# 2-psg-plain2.net
KiCad netlist of a schematic drawn in EAGLE
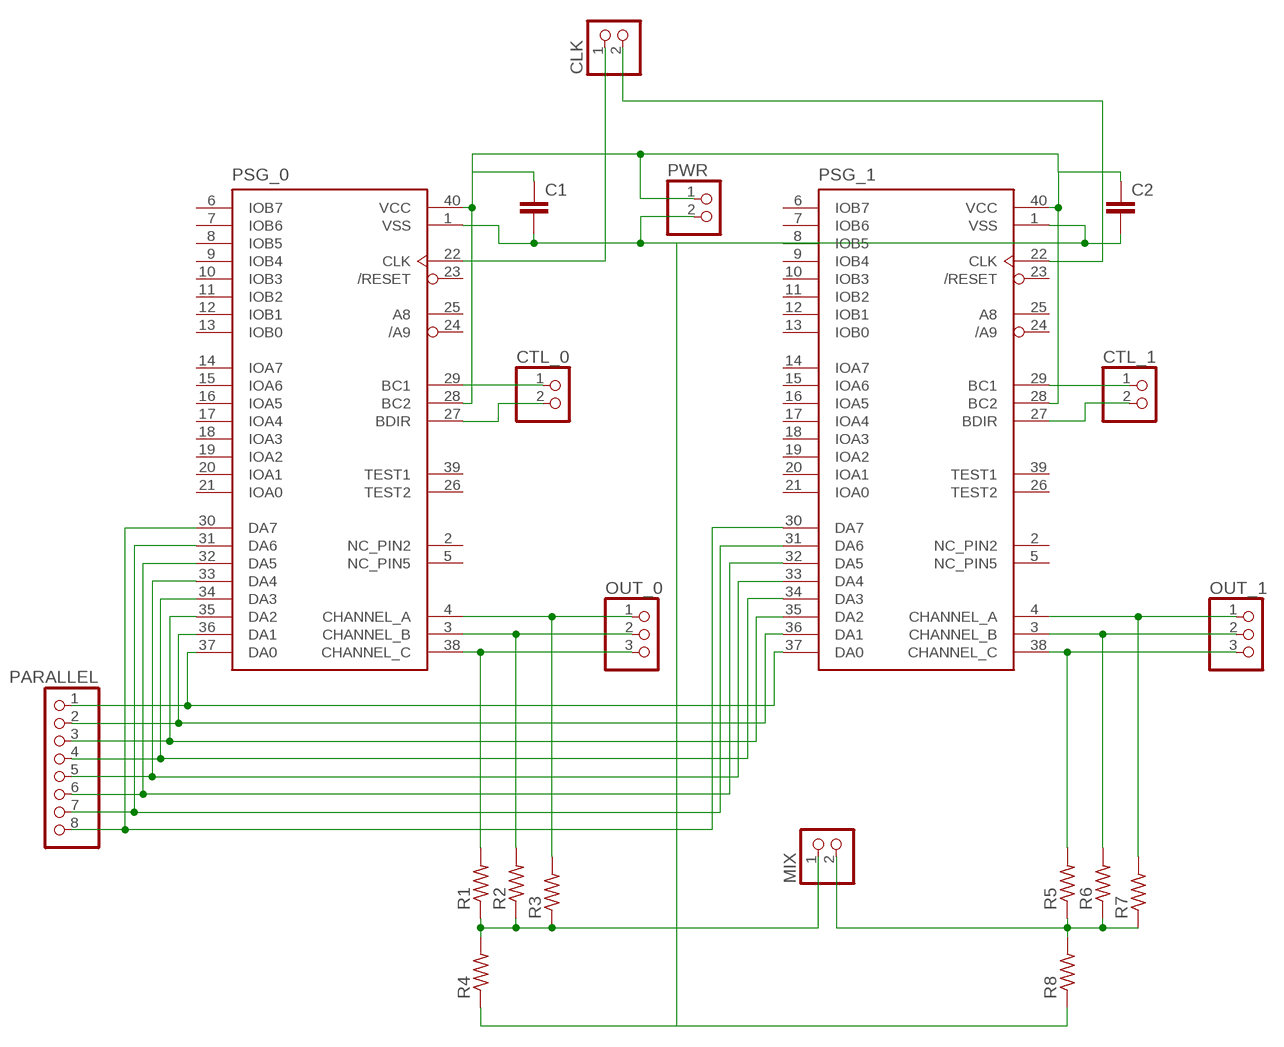
[diagram p0: schematic, sheet 1]

(export (version "E")
  (design (tool "Eeschema 10.0.6"))
  (components
    (comp (ref "C1")
      (value "050X030_0251")
      (footprint "eagle-import:050X030_025")
      (libsource (lib "eagle-import") (part "050X030_0251"))
    )
    (comp (ref "C2")
      (value "050X030_0251")
      (footprint "eagle-import:050X030_025")
      (libsource (lib "eagle-import") (part "050X030_0251"))
    )
    (comp (ref "CLK")
      (value "PINHD-1X2")
      (footprint "eagle-import:1X02")
      (libsource (lib "eagle-import") (part "PINHD-1X2"))
    )
    (comp (ref "CTL_0")
      (value "PINHD-1X2")
      (footprint "eagle-import:1X02")
      (libsource (lib "eagle-import") (part "PINHD-1X2"))
    )
    (comp (ref "CTL_1")
      (value "PINHD-1X2")
      (footprint "eagle-import:1X02")
      (libsource (lib "eagle-import") (part "PINHD-1X2"))
    )
    (comp (ref "MIX")
      (value "PINHD-1X2")
      (footprint "eagle-import:1X02")
      (libsource (lib "eagle-import") (part "PINHD-1X2"))
    )
    (comp (ref "OUT_0")
      (value "PINHD-1X3")
      (footprint "eagle-import:1X03")
      (libsource (lib "eagle-import") (part "PINHD-1X3"))
    )
    (comp (ref "OUT_1")
      (value "PINHD-1X3")
      (footprint "eagle-import:1X03")
      (libsource (lib "eagle-import") (part "PINHD-1X3"))
    )
    (comp (ref "PARALLEL")
      (value "PINHD-1X8")
      (footprint "eagle-import:1X08")
      (libsource (lib "eagle-import") (part "PINHD-1X8"))
    )
    (comp (ref "PSG_0")
      (value "AY-3-8910")
      (footprint "eagle-import:DIL40")
      (libsource (lib "eagle-import") (part "AY-3-8910"))
    )
    (comp (ref "PSG_1")
      (value "AY-3-8910")
      (footprint "eagle-import:DIL40")
      (libsource (lib "eagle-import") (part "AY-3-8910"))
    )
    (comp (ref "PWR")
      (value "PINHD-1X2")
      (footprint "eagle-import:1X02")
      (libsource (lib "eagle-import") (part "PINHD-1X2"))
    )
    (comp (ref "R1")
      (value "6MM.3")
      (footprint "eagle-import:R0207_3")
      (libsource (lib "eagle-import") (part "6MM.3"))
    )
    (comp (ref "R2")
      (value "6MM.3")
      (footprint "eagle-import:R0207_3")
      (libsource (lib "eagle-import") (part "6MM.3"))
    )
    (comp (ref "R3")
      (value "6MM.3")
      (footprint "eagle-import:R0207_3")
      (libsource (lib "eagle-import") (part "6MM.3"))
    )
    (comp (ref "R4")
      (value "6MM.3")
      (footprint "eagle-import:R0207_3")
      (libsource (lib "eagle-import") (part "6MM.3"))
    )
    (comp (ref "R5")
      (value "6MM.3")
      (footprint "eagle-import:R0207_3")
      (libsource (lib "eagle-import") (part "6MM.3"))
    )
    (comp (ref "R6")
      (value "6MM.3")
      (footprint "eagle-import:R0207_3")
      (libsource (lib "eagle-import") (part "6MM.3"))
    )
    (comp (ref "R7")
      (value "6MM.3")
      (footprint "eagle-import:R0207_3")
      (libsource (lib "eagle-import") (part "6MM.3"))
    )
    (comp (ref "R8")
      (value "6MM.3")
      (footprint "eagle-import:R0207_3")
      (libsource (lib "eagle-import") (part "6MM.3"))
    )
  )
  (nets
    (net (code "1") (name "Net-(MIX-Pad1)") (class "Default")
      (node (ref "MIX") (pin "1") (pinfunction "1_1") (pintype "passive"))
      (node (ref "R1") (pin "1") (pinfunction "1_1") (pintype "passive"))
      (node (ref "R2") (pin "1") (pinfunction "1_1") (pintype "passive"))
      (node (ref "R3") (pin "1") (pinfunction "1_1") (pintype "passive"))
      (node (ref "R4") (pin "2") (pinfunction "2_2") (pintype "passive"))
    )
    (net (code "2") (name "Net-(MIX-Pad2)") (class "Default")
      (node (ref "MIX") (pin "2") (pinfunction "2_2") (pintype "passive"))
      (node (ref "R5") (pin "1") (pinfunction "1_1") (pintype "passive"))
      (node (ref "R6") (pin "1") (pinfunction "1_1") (pintype "passive"))
      (node (ref "R7") (pin "1") (pinfunction "1_1") (pintype "passive"))
      (node (ref "R8") (pin "2") (pinfunction "2_2") (pintype "passive"))
    )
    (net (code "3") (name "Net-(PSG_0-BC1)") (class "Default")
      (node (ref "CTL_0") (pin "1") (pinfunction "1_1") (pintype "passive"))
      (node (ref "PSG_0") (pin "29") (pinfunction "BC1_29") (pintype "input"))
    )
    (net (code "4") (name "Net-(PSG_0-BC2)") (class "Default")
      (node (ref "C1") (pin "1") (pinfunction "1_1") (pintype "passive"))
      (node (ref "C2") (pin "1") (pinfunction "1_1") (pintype "passive"))
      (node (ref "PSG_0") (pin "28") (pinfunction "BC2_28") (pintype "input"))
      (node (ref "PSG_0") (pin "40") (pinfunction "VCC_40") (pintype "power_in"))
      (node (ref "PSG_1") (pin "28") (pinfunction "BC2_28") (pintype "input"))
      (node (ref "PSG_1") (pin "40") (pinfunction "VCC_40") (pintype "power_in"))
      (node (ref "PWR") (pin "1") (pinfunction "1_1") (pintype "passive"))
    )
    (net (code "5") (name "Net-(PSG_0-BDIR)") (class "Default")
      (node (ref "CTL_0") (pin "2") (pinfunction "2_2") (pintype "passive"))
      (node (ref "PSG_0") (pin "27") (pinfunction "BDIR_27") (pintype "input"))
    )
    (net (code "6") (name "Net-(PSG_0-CHANNEL_A)") (class "Default")
      (node (ref "OUT_0") (pin "1") (pinfunction "1_1") (pintype "passive"))
      (node (ref "PSG_0") (pin "4") (pinfunction "CHANNEL_A_4") (pintype "output"))
      (node (ref "R3") (pin "2") (pinfunction "2_2") (pintype "passive"))
    )
    (net (code "7") (name "Net-(PSG_0-CHANNEL_B)") (class "Default")
      (node (ref "OUT_0") (pin "2") (pinfunction "2_2") (pintype "passive"))
      (node (ref "PSG_0") (pin "3") (pinfunction "CHANNEL_B_3") (pintype "output"))
      (node (ref "R2") (pin "2") (pinfunction "2_2") (pintype "passive"))
    )
    (net (code "8") (name "Net-(PSG_0-CHANNEL_C)") (class "Default")
      (node (ref "OUT_0") (pin "3") (pinfunction "3_3") (pintype "passive"))
      (node (ref "PSG_0") (pin "38") (pinfunction "CHANNEL_C_38") (pintype "output"))
      (node (ref "R1") (pin "2") (pinfunction "2_2") (pintype "passive"))
    )
    (net (code "9") (name "Net-(PSG_0-CLK)") (class "Default")
      (node (ref "CLK") (pin "1") (pinfunction "1_1") (pintype "passive"))
      (node (ref "PSG_0") (pin "22") (pinfunction "CLK_22") (pintype "input"))
    )
    (net (code "10") (name "Net-(PSG_0-DA0)") (class "Default")
      (node (ref "PARALLEL") (pin "1") (pinfunction "1_1") (pintype "passive"))
      (node (ref "PSG_0") (pin "37") (pinfunction "DA0_37") (pintype "bidirectional"))
      (node (ref "PSG_1") (pin "37") (pinfunction "DA0_37") (pintype "bidirectional"))
    )
    (net (code "11") (name "Net-(PSG_0-DA1)") (class "Default")
      (node (ref "PARALLEL") (pin "2") (pinfunction "2_2") (pintype "passive"))
      (node (ref "PSG_0") (pin "36") (pinfunction "DA1_36") (pintype "bidirectional"))
      (node (ref "PSG_1") (pin "36") (pinfunction "DA1_36") (pintype "bidirectional"))
    )
    (net (code "12") (name "Net-(PSG_0-DA2)") (class "Default")
      (node (ref "PARALLEL") (pin "3") (pinfunction "3_3") (pintype "passive"))
      (node (ref "PSG_0") (pin "35") (pinfunction "DA2_35") (pintype "bidirectional"))
      (node (ref "PSG_1") (pin "35") (pinfunction "DA2_35") (pintype "bidirectional"))
    )
    (net (code "13") (name "Net-(PSG_0-DA3)") (class "Default")
      (node (ref "PARALLEL") (pin "4") (pinfunction "4_4") (pintype "passive"))
      (node (ref "PSG_0") (pin "34") (pinfunction "DA3_34") (pintype "bidirectional"))
      (node (ref "PSG_1") (pin "34") (pinfunction "DA3_34") (pintype "bidirectional"))
    )
    (net (code "14") (name "Net-(PSG_0-DA4)") (class "Default")
      (node (ref "PARALLEL") (pin "5") (pinfunction "5_5") (pintype "passive"))
      (node (ref "PSG_0") (pin "33") (pinfunction "DA4_33") (pintype "bidirectional"))
      (node (ref "PSG_1") (pin "33") (pinfunction "DA4_33") (pintype "bidirectional"))
    )
    (net (code "15") (name "Net-(PSG_0-DA5)") (class "Default")
      (node (ref "PARALLEL") (pin "6") (pinfunction "6_6") (pintype "passive"))
      (node (ref "PSG_0") (pin "32") (pinfunction "DA5_32") (pintype "bidirectional"))
      (node (ref "PSG_1") (pin "32") (pinfunction "DA5_32") (pintype "bidirectional"))
    )
    (net (code "16") (name "Net-(PSG_0-DA6)") (class "Default")
      (node (ref "PARALLEL") (pin "7") (pinfunction "7_7") (pintype "passive"))
      (node (ref "PSG_0") (pin "31") (pinfunction "DA6_31") (pintype "bidirectional"))
      (node (ref "PSG_1") (pin "31") (pinfunction "DA6_31") (pintype "bidirectional"))
    )
    (net (code "17") (name "Net-(PSG_0-DA7)") (class "Default")
      (node (ref "PARALLEL") (pin "8") (pinfunction "8_8") (pintype "passive"))
      (node (ref "PSG_0") (pin "30") (pinfunction "DA7_30") (pintype "bidirectional"))
      (node (ref "PSG_1") (pin "30") (pinfunction "DA7_30") (pintype "bidirectional"))
    )
    (net (code "18") (name "Net-(PSG_0-VSS)") (class "Default")
      (node (ref "C1") (pin "2") (pinfunction "2_2") (pintype "passive"))
      (node (ref "C2") (pin "2") (pinfunction "2_2") (pintype "passive"))
      (node (ref "PSG_0") (pin "1") (pinfunction "VSS_1") (pintype "power_in"))
      (node (ref "PSG_1") (pin "1") (pinfunction "VSS_1") (pintype "power_in"))
      (node (ref "PWR") (pin "2") (pinfunction "2_2") (pintype "passive"))
      (node (ref "R4") (pin "1") (pinfunction "1_1") (pintype "passive"))
      (node (ref "R8") (pin "1") (pinfunction "1_1") (pintype "passive"))
    )
    (net (code "19") (name "Net-(PSG_1-BC1)") (class "Default")
      (node (ref "CTL_1") (pin "1") (pinfunction "1_1") (pintype "passive"))
      (node (ref "PSG_1") (pin "29") (pinfunction "BC1_29") (pintype "input"))
    )
    (net (code "20") (name "Net-(PSG_1-BDIR)") (class "Default")
      (node (ref "CTL_1") (pin "2") (pinfunction "2_2") (pintype "passive"))
      (node (ref "PSG_1") (pin "27") (pinfunction "BDIR_27") (pintype "input"))
    )
    (net (code "21") (name "Net-(PSG_1-CHANNEL_A)") (class "Default")
      (node (ref "OUT_1") (pin "1") (pinfunction "1_1") (pintype "passive"))
      (node (ref "PSG_1") (pin "4") (pinfunction "CHANNEL_A_4") (pintype "output"))
      (node (ref "R7") (pin "2") (pinfunction "2_2") (pintype "passive"))
    )
    (net (code "22") (name "Net-(PSG_1-CHANNEL_B)") (class "Default")
      (node (ref "OUT_1") (pin "2") (pinfunction "2_2") (pintype "passive"))
      (node (ref "PSG_1") (pin "3") (pinfunction "CHANNEL_B_3") (pintype "output"))
      (node (ref "R6") (pin "2") (pinfunction "2_2") (pintype "passive"))
    )
    (net (code "23") (name "Net-(PSG_1-CHANNEL_C)") (class "Default")
      (node (ref "OUT_1") (pin "3") (pinfunction "3_3") (pintype "passive"))
      (node (ref "PSG_1") (pin "38") (pinfunction "CHANNEL_C_38") (pintype "output"))
      (node (ref "R5") (pin "2") (pinfunction "2_2") (pintype "passive"))
    )
    (net (code "24") (name "Net-(PSG_1-CLK)") (class "Default")
      (node (ref "CLK") (pin "2") (pinfunction "2_2") (pintype "passive"))
      (node (ref "PSG_1") (pin "22") (pinfunction "CLK_22") (pintype "input"))
    )
    (net (code "25") (name "unconnected-(PSG_0-A8-Pad25)") (class "Default")
      (node (ref "PSG_0") (pin "25") (pinfunction "A8_25") (pintype "bidirectional"))
    )
    (net (code "26") (name "unconnected-(PSG_0-IOA0-Pad21)") (class "Default")
      (node (ref "PSG_0") (pin "21") (pinfunction "IOA0_21") (pintype "bidirectional"))
    )
    (net (code "27") (name "unconnected-(PSG_0-IOA1-Pad20)") (class "Default")
      (node (ref "PSG_0") (pin "20") (pinfunction "IOA1_20") (pintype "bidirectional"))
    )
    (net (code "28") (name "unconnected-(PSG_0-IOA2-Pad19)") (class "Default")
      (node (ref "PSG_0") (pin "19") (pinfunction "IOA2_19") (pintype "bidirectional"))
    )
    (net (code "29") (name "unconnected-(PSG_0-IOA3-Pad18)") (class "Default")
      (node (ref "PSG_0") (pin "18") (pinfunction "IOA3_18") (pintype "bidirectional"))
    )
    (net (code "30") (name "unconnected-(PSG_0-IOA4-Pad17)") (class "Default")
      (node (ref "PSG_0") (pin "17") (pinfunction "IOA4_17") (pintype "bidirectional"))
    )
    (net (code "31") (name "unconnected-(PSG_0-IOA5-Pad16)") (class "Default")
      (node (ref "PSG_0") (pin "16") (pinfunction "IOA5_16") (pintype "bidirectional"))
    )
    (net (code "32") (name "unconnected-(PSG_0-IOA6-Pad15)") (class "Default")
      (node (ref "PSG_0") (pin "15") (pinfunction "IOA6_15") (pintype "bidirectional"))
    )
    (net (code "33") (name "unconnected-(PSG_0-IOA7-Pad14)") (class "Default")
      (node (ref "PSG_0") (pin "14") (pinfunction "IOA7_14") (pintype "bidirectional"))
    )
    (net (code "34") (name "unconnected-(PSG_0-IOB0-Pad13)") (class "Default")
      (node (ref "PSG_0") (pin "13") (pinfunction "IOB0_13") (pintype "bidirectional"))
    )
    (net (code "35") (name "unconnected-(PSG_0-IOB1-Pad12)") (class "Default")
      (node (ref "PSG_0") (pin "12") (pinfunction "IOB1_12") (pintype "bidirectional"))
    )
    (net (code "36") (name "unconnected-(PSG_0-IOB2-Pad11)") (class "Default")
      (node (ref "PSG_0") (pin "11") (pinfunction "IOB2_11") (pintype "bidirectional"))
    )
    (net (code "37") (name "unconnected-(PSG_0-IOB3-Pad10)") (class "Default")
      (node (ref "PSG_0") (pin "10") (pinfunction "IOB3_10") (pintype "bidirectional"))
    )
    (net (code "38") (name "unconnected-(PSG_0-IOB4-Pad9)") (class "Default")
      (node (ref "PSG_0") (pin "9") (pinfunction "IOB4_9") (pintype "bidirectional"))
    )
    (net (code "39") (name "unconnected-(PSG_0-IOB5-Pad8)") (class "Default")
      (node (ref "PSG_0") (pin "8") (pinfunction "IOB5_8") (pintype "bidirectional"))
    )
    (net (code "40") (name "unconnected-(PSG_0-IOB6-Pad7)") (class "Default")
      (node (ref "PSG_0") (pin "7") (pinfunction "IOB6_7") (pintype "bidirectional"))
    )
    (net (code "41") (name "unconnected-(PSG_0-IOB7-Pad6)") (class "Default")
      (node (ref "PSG_0") (pin "6") (pinfunction "IOB7_6") (pintype "bidirectional"))
    )
    (net (code "42") (name "unconnected-(PSG_0-NC_PIN2-Pad2)") (class "Default")
      (node (ref "PSG_0") (pin "2") (pinfunction "NC_PIN2_2") (pintype "no_connect"))
    )
    (net (code "43") (name "unconnected-(PSG_0-NC_PIN5-Pad5)") (class "Default")
      (node (ref "PSG_0") (pin "5") (pinfunction "NC_PIN5_5") (pintype "bidirectional"))
    )
    (net (code "44") (name "unconnected-(PSG_0-TEST1-Pad39)") (class "Default")
      (node (ref "PSG_0") (pin "39") (pinfunction "TEST1_39") (pintype "no_connect"))
    )
    (net (code "45") (name "unconnected-(PSG_0-TEST2-Pad26)") (class "Default")
      (node (ref "PSG_0") (pin "26") (pinfunction "TEST2_26") (pintype "no_connect"))
    )
    (net (code "46") (name "unconnected-(PSG_0-{slash}A9-Pad24)") (class "Default")
      (node (ref "PSG_0") (pin "24") (pinfunction "/A9_24") (pintype "bidirectional"))
    )
    (net (code "47") (name "unconnected-(PSG_0-{slash}RESET-Pad23)") (class "Default")
      (node (ref "PSG_0") (pin "23") (pinfunction "/RESET_23") (pintype "input"))
    )
    (net (code "48") (name "unconnected-(PSG_1-A8-Pad25)") (class "Default")
      (node (ref "PSG_1") (pin "25") (pinfunction "A8_25") (pintype "bidirectional"))
    )
    (net (code "49") (name "unconnected-(PSG_1-IOA0-Pad21)") (class "Default")
      (node (ref "PSG_1") (pin "21") (pinfunction "IOA0_21") (pintype "bidirectional"))
    )
    (net (code "50") (name "unconnected-(PSG_1-IOA1-Pad20)") (class "Default")
      (node (ref "PSG_1") (pin "20") (pinfunction "IOA1_20") (pintype "bidirectional"))
    )
    (net (code "51") (name "unconnected-(PSG_1-IOA2-Pad19)") (class "Default")
      (node (ref "PSG_1") (pin "19") (pinfunction "IOA2_19") (pintype "bidirectional"))
    )
    (net (code "52") (name "unconnected-(PSG_1-IOA3-Pad18)") (class "Default")
      (node (ref "PSG_1") (pin "18") (pinfunction "IOA3_18") (pintype "bidirectional"))
    )
    (net (code "53") (name "unconnected-(PSG_1-IOA4-Pad17)") (class "Default")
      (node (ref "PSG_1") (pin "17") (pinfunction "IOA4_17") (pintype "bidirectional"))
    )
    (net (code "54") (name "unconnected-(PSG_1-IOA5-Pad16)") (class "Default")
      (node (ref "PSG_1") (pin "16") (pinfunction "IOA5_16") (pintype "bidirectional"))
    )
    (net (code "55") (name "unconnected-(PSG_1-IOA6-Pad15)") (class "Default")
      (node (ref "PSG_1") (pin "15") (pinfunction "IOA6_15") (pintype "bidirectional"))
    )
    (net (code "56") (name "unconnected-(PSG_1-IOA7-Pad14)") (class "Default")
      (node (ref "PSG_1") (pin "14") (pinfunction "IOA7_14") (pintype "bidirectional"))
    )
    (net (code "57") (name "unconnected-(PSG_1-IOB0-Pad13)") (class "Default")
      (node (ref "PSG_1") (pin "13") (pinfunction "IOB0_13") (pintype "bidirectional"))
    )
    (net (code "58") (name "unconnected-(PSG_1-IOB1-Pad12)") (class "Default")
      (node (ref "PSG_1") (pin "12") (pinfunction "IOB1_12") (pintype "bidirectional"))
    )
    (net (code "59") (name "unconnected-(PSG_1-IOB2-Pad11)") (class "Default")
      (node (ref "PSG_1") (pin "11") (pinfunction "IOB2_11") (pintype "bidirectional"))
    )
    (net (code "60") (name "unconnected-(PSG_1-IOB3-Pad10)") (class "Default")
      (node (ref "PSG_1") (pin "10") (pinfunction "IOB3_10") (pintype "bidirectional"))
    )
    (net (code "61") (name "unconnected-(PSG_1-IOB4-Pad9)") (class "Default")
      (node (ref "PSG_1") (pin "9") (pinfunction "IOB4_9") (pintype "bidirectional"))
    )
    (net (code "62") (name "unconnected-(PSG_1-IOB5-Pad8)") (class "Default")
      (node (ref "PSG_1") (pin "8") (pinfunction "IOB5_8") (pintype "bidirectional"))
    )
    (net (code "63") (name "unconnected-(PSG_1-IOB6-Pad7)") (class "Default")
      (node (ref "PSG_1") (pin "7") (pinfunction "IOB6_7") (pintype "bidirectional"))
    )
    (net (code "64") (name "unconnected-(PSG_1-IOB7-Pad6)") (class "Default")
      (node (ref "PSG_1") (pin "6") (pinfunction "IOB7_6") (pintype "bidirectional"))
    )
    (net (code "65") (name "unconnected-(PSG_1-NC_PIN2-Pad2)") (class "Default")
      (node (ref "PSG_1") (pin "2") (pinfunction "NC_PIN2_2") (pintype "no_connect"))
    )
    (net (code "66") (name "unconnected-(PSG_1-NC_PIN5-Pad5)") (class "Default")
      (node (ref "PSG_1") (pin "5") (pinfunction "NC_PIN5_5") (pintype "bidirectional"))
    )
    (net (code "67") (name "unconnected-(PSG_1-TEST1-Pad39)") (class "Default")
      (node (ref "PSG_1") (pin "39") (pinfunction "TEST1_39") (pintype "no_connect"))
    )
    (net (code "68") (name "unconnected-(PSG_1-TEST2-Pad26)") (class "Default")
      (node (ref "PSG_1") (pin "26") (pinfunction "TEST2_26") (pintype "no_connect"))
    )
    (net (code "69") (name "unconnected-(PSG_1-{slash}A9-Pad24)") (class "Default")
      (node (ref "PSG_1") (pin "24") (pinfunction "/A9_24") (pintype "bidirectional"))
    )
    (net (code "70") (name "unconnected-(PSG_1-{slash}RESET-Pad23)") (class "Default")
      (node (ref "PSG_1") (pin "23") (pinfunction "/RESET_23") (pintype "input"))
    )
  )
)
